# OperantFEDv5.net
KiCad netlist of a schematic drawn in EAGLE
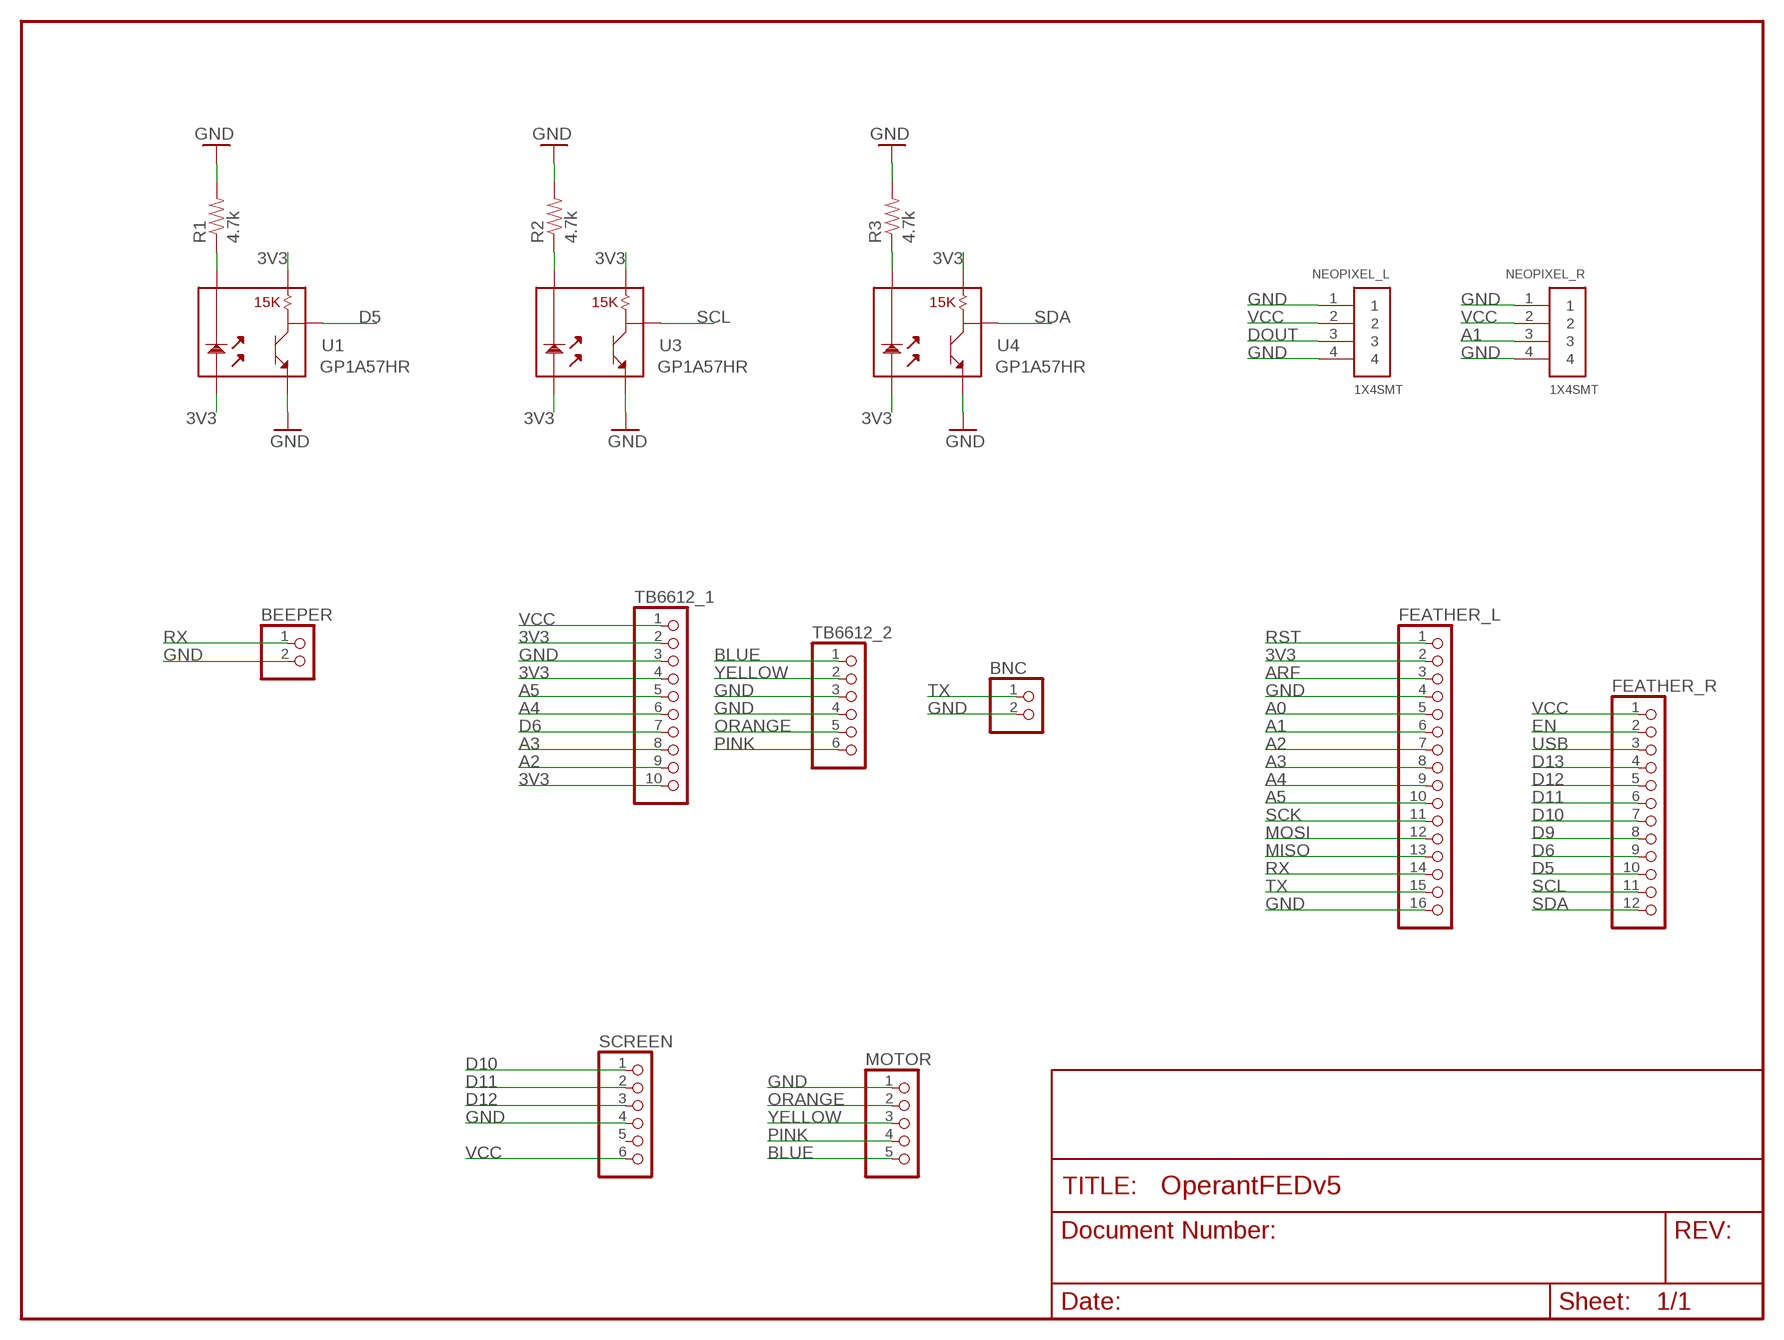
[diagram p0: schematic, sheet 1]

(export (version "E")
  (design (tool "Eeschema 10.0.6"))
  (components
    (comp (ref "BEEPER")
      (value "PINHD-1X2")
      (footprint "eagle-import:1X02")
      (libsource (lib "eagle-import") (part "PINHD-1X2"))
    )
    (comp (ref "BNC")
      (value "PINHD-1X2")
      (footprint "eagle-import:1X02")
      (libsource (lib "eagle-import") (part "PINHD-1X2"))
    )
    (comp (ref "FEATHER_L")
      (value "PINHD-1X16")
      (footprint "eagle-import:1X16")
      (libsource (lib "eagle-import") (part "PINHD-1X16"))
    )
    (comp (ref "FEATHER_R")
      (value "PINHD-1X12")
      (footprint "eagle-import:1X12")
      (libsource (lib "eagle-import") (part "PINHD-1X12"))
    )
    (comp (ref "MOTOR")
      (value "PINHD-1X5")
      (footprint "eagle-import:1X05")
      (libsource (lib "eagle-import") (part "PINHD-1X5"))
    )
    (comp (ref "NEOPIXEL_L")
      (value "1X4SMT")
      (footprint "eagle-import:1X4-SMT")
      (libsource (lib "eagle-import") (part "1X4SMT"))
    )
    (comp (ref "NEOPIXEL_R")
      (value "1X4SMT")
      (footprint "eagle-import:1X4-SMT")
      (libsource (lib "eagle-import") (part "1X4SMT"))
    )
    (comp (ref "R1")
      (value "4.7k")
      (footprint "eagle-import:AXIAL-0.3")
      (libsource (lib "eagle-import") (part "RESISTORPTH1"))
    )
    (comp (ref "R2")
      (value "4.7k")
      (footprint "eagle-import:AXIAL-0.3")
      (libsource (lib "eagle-import") (part "RESISTORPTH1"))
    )
    (comp (ref "R3")
      (value "4.7k")
      (footprint "eagle-import:AXIAL-0.3")
      (libsource (lib "eagle-import") (part "RESISTORPTH1"))
    )
    (comp (ref "SCREEN")
      (value "PINHD-1X6")
      (footprint "eagle-import:1X06")
      (libsource (lib "eagle-import") (part "PINHD-1X6"))
    )
    (comp (ref "TB6612_1")
      (value "PINHD-1X10")
      (footprint "eagle-import:1X10")
      (libsource (lib "eagle-import") (part "PINHD-1X10"))
    )
    (comp (ref "TB6612_2")
      (value "PINHD-1X6")
      (footprint "eagle-import:1X06")
      (libsource (lib "eagle-import") (part "PINHD-1X6"))
    )
    (comp (ref "U1")
      (value "GP1A57HR")
      (footprint "eagle-import:GP1A57HR")
      (libsource (lib "eagle-import") (part "GP1A57HR"))
    )
    (comp (ref "U3")
      (value "GP1A57HR")
      (footprint "eagle-import:GP1A57HR")
      (libsource (lib "eagle-import") (part "GP1A57HR"))
    )
    (comp (ref "U4")
      (value "GP1A57HR")
      (footprint "eagle-import:GP1A57HR")
      (libsource (lib "eagle-import") (part "GP1A57HR"))
    )
  )
  (nets
    (net (code "1") (name "/3V3") (class "Default")
      (node (ref "FEATHER_L") (pin "2") (pinfunction "2_2") (pintype "passive"))
      (node (ref "TB6612_1") (pin "10") (pinfunction "10_10") (pintype "passive"))
      (node (ref "TB6612_1") (pin "2") (pinfunction "2_2") (pintype "passive"))
      (node (ref "TB6612_1") (pin "4") (pinfunction "4_4") (pintype "passive"))
      (node (ref "U1") (pin "1") (pinfunction "1_1") (pintype "bidirectional"))
      (node (ref "U1") (pin "3") (pinfunction "3_3") (pintype "bidirectional"))
      (node (ref "U3") (pin "1") (pinfunction "1_1") (pintype "bidirectional"))
      (node (ref "U3") (pin "3") (pinfunction "3_3") (pintype "bidirectional"))
      (node (ref "U4") (pin "1") (pinfunction "1_1") (pintype "bidirectional"))
      (node (ref "U4") (pin "3") (pinfunction "3_3") (pintype "bidirectional"))
    )
    (net (code "2") (name "/A0") (class "Default")
      (node (ref "FEATHER_L") (pin "5") (pinfunction "5_5") (pintype "passive"))
    )
    (net (code "3") (name "/A1") (class "Default")
      (node (ref "FEATHER_L") (pin "6") (pinfunction "6_6") (pintype "passive"))
      (node (ref "NEOPIXEL_R") (pin "3") (pinfunction "3_3") (pintype "bidirectional"))
    )
    (net (code "4") (name "/A2") (class "Default")
      (node (ref "FEATHER_L") (pin "7") (pinfunction "7_7") (pintype "passive"))
      (node (ref "TB6612_1") (pin "9") (pinfunction "9_9") (pintype "passive"))
    )
    (net (code "5") (name "/A3") (class "Default")
      (node (ref "FEATHER_L") (pin "8") (pinfunction "8_8") (pintype "passive"))
      (node (ref "TB6612_1") (pin "8") (pinfunction "8_8") (pintype "passive"))
    )
    (net (code "6") (name "/A4") (class "Default")
      (node (ref "FEATHER_L") (pin "9") (pinfunction "9_9") (pintype "passive"))
      (node (ref "TB6612_1") (pin "6") (pinfunction "6_6") (pintype "passive"))
    )
    (net (code "7") (name "/A5") (class "Default")
      (node (ref "FEATHER_L") (pin "10") (pinfunction "10_10") (pintype "passive"))
      (node (ref "TB6612_1") (pin "5") (pinfunction "5_5") (pintype "passive"))
    )
    (net (code "8") (name "/ARF") (class "Default")
      (node (ref "FEATHER_L") (pin "3") (pinfunction "3_3") (pintype "passive"))
    )
    (net (code "9") (name "/BLUE") (class "Default")
      (node (ref "MOTOR") (pin "5") (pinfunction "5_5") (pintype "passive"))
      (node (ref "TB6612_2") (pin "1") (pinfunction "1_1") (pintype "passive"))
    )
    (net (code "10") (name "/D5") (class "Default")
      (node (ref "FEATHER_R") (pin "10") (pinfunction "10_10") (pintype "passive"))
      (node (ref "U1") (pin "4") (pinfunction "4_4") (pintype "bidirectional"))
    )
    (net (code "11") (name "/D6") (class "Default")
      (node (ref "FEATHER_R") (pin "9") (pinfunction "9_9") (pintype "passive"))
      (node (ref "TB6612_1") (pin "7") (pinfunction "7_7") (pintype "passive"))
    )
    (net (code "12") (name "/D9") (class "Default")
      (node (ref "FEATHER_R") (pin "8") (pinfunction "8_8") (pintype "passive"))
    )
    (net (code "13") (name "/D10") (class "Default")
      (node (ref "FEATHER_R") (pin "7") (pinfunction "7_7") (pintype "passive"))
      (node (ref "SCREEN") (pin "1") (pinfunction "1_1") (pintype "passive"))
    )
    (net (code "14") (name "/D11") (class "Default")
      (node (ref "FEATHER_R") (pin "6") (pinfunction "6_6") (pintype "passive"))
      (node (ref "SCREEN") (pin "2") (pinfunction "2_2") (pintype "passive"))
    )
    (net (code "15") (name "/D12") (class "Default")
      (node (ref "FEATHER_R") (pin "5") (pinfunction "5_5") (pintype "passive"))
      (node (ref "SCREEN") (pin "3") (pinfunction "3_3") (pintype "passive"))
    )
    (net (code "16") (name "/D13") (class "Default")
      (node (ref "FEATHER_R") (pin "4") (pinfunction "4_4") (pintype "passive"))
    )
    (net (code "17") (name "/DOUT") (class "Default")
      (node (ref "NEOPIXEL_L") (pin "3") (pinfunction "3_3") (pintype "bidirectional"))
    )
    (net (code "18") (name "/EN") (class "Default")
      (node (ref "FEATHER_R") (pin "2") (pinfunction "2_2") (pintype "passive"))
    )
    (net (code "19") (name "/MISO") (class "Default")
      (node (ref "FEATHER_L") (pin "13") (pinfunction "13_13") (pintype "passive"))
    )
    (net (code "20") (name "/MOSI") (class "Default")
      (node (ref "FEATHER_L") (pin "12") (pinfunction "12_12") (pintype "passive"))
    )
    (net (code "21") (name "/ORANGE") (class "Default")
      (node (ref "MOTOR") (pin "2") (pinfunction "2_2") (pintype "passive"))
      (node (ref "TB6612_2") (pin "5") (pinfunction "5_5") (pintype "passive"))
    )
    (net (code "22") (name "/PINK") (class "Default")
      (node (ref "MOTOR") (pin "4") (pinfunction "4_4") (pintype "passive"))
      (node (ref "TB6612_2") (pin "6") (pinfunction "6_6") (pintype "passive"))
    )
    (net (code "23") (name "/RST") (class "Default")
      (node (ref "FEATHER_L") (pin "1") (pinfunction "1_1") (pintype "passive"))
    )
    (net (code "24") (name "/RX") (class "Default")
      (node (ref "BEEPER") (pin "1") (pinfunction "1_1") (pintype "passive"))
      (node (ref "FEATHER_L") (pin "14") (pinfunction "14_14") (pintype "passive"))
    )
    (net (code "25") (name "/SCK") (class "Default")
      (node (ref "FEATHER_L") (pin "11") (pinfunction "11_11") (pintype "passive"))
    )
    (net (code "26") (name "/SCL") (class "Default")
      (node (ref "FEATHER_R") (pin "11") (pinfunction "11_11") (pintype "passive"))
      (node (ref "U3") (pin "4") (pinfunction "4_4") (pintype "bidirectional"))
    )
    (net (code "27") (name "/SDA") (class "Default")
      (node (ref "FEATHER_R") (pin "12") (pinfunction "12_12") (pintype "passive"))
      (node (ref "U4") (pin "4") (pinfunction "4_4") (pintype "bidirectional"))
    )
    (net (code "28") (name "/TX") (class "Default")
      (node (ref "BNC") (pin "1") (pinfunction "1_1") (pintype "passive"))
      (node (ref "FEATHER_L") (pin "15") (pinfunction "15_15") (pintype "passive"))
    )
    (net (code "29") (name "/USB") (class "Default")
      (node (ref "FEATHER_R") (pin "3") (pinfunction "3_3") (pintype "passive"))
    )
    (net (code "30") (name "/VCC") (class "Default")
      (node (ref "FEATHER_R") (pin "1") (pinfunction "1_1") (pintype "passive"))
      (node (ref "NEOPIXEL_L") (pin "2") (pinfunction "2_2") (pintype "bidirectional"))
      (node (ref "NEOPIXEL_R") (pin "2") (pinfunction "2_2") (pintype "bidirectional"))
      (node (ref "SCREEN") (pin "6") (pinfunction "6_6") (pintype "passive"))
      (node (ref "TB6612_1") (pin "1") (pinfunction "1_1") (pintype "passive"))
    )
    (net (code "31") (name "/YELLOW") (class "Default")
      (node (ref "MOTOR") (pin "3") (pinfunction "3_3") (pintype "passive"))
      (node (ref "TB6612_2") (pin "2") (pinfunction "2_2") (pintype "passive"))
    )
    (net (code "32") (name "GND") (class "Default")
      (node (ref "BEEPER") (pin "2") (pinfunction "2_2") (pintype "passive"))
      (node (ref "BNC") (pin "2") (pinfunction "2_2") (pintype "passive"))
      (node (ref "FEATHER_L") (pin "16") (pinfunction "16_16") (pintype "passive"))
      (node (ref "FEATHER_L") (pin "4") (pinfunction "4_4") (pintype "passive"))
      (node (ref "MOTOR") (pin "1") (pinfunction "1_1") (pintype "passive"))
      (node (ref "NEOPIXEL_L") (pin "1") (pinfunction "1_1") (pintype "bidirectional"))
      (node (ref "NEOPIXEL_L") (pin "4") (pinfunction "4_4") (pintype "bidirectional"))
      (node (ref "NEOPIXEL_R") (pin "1") (pinfunction "1_1") (pintype "bidirectional"))
      (node (ref "NEOPIXEL_R") (pin "4") (pinfunction "4_4") (pintype "bidirectional"))
      (node (ref "R1") (pin "P$2") (pinfunction "2_P$2") (pintype "passive"))
      (node (ref "R2") (pin "P$2") (pinfunction "2_P$2") (pintype "passive"))
      (node (ref "R3") (pin "P$2") (pinfunction "2_P$2") (pintype "passive"))
      (node (ref "SCREEN") (pin "4") (pinfunction "4_4") (pintype "passive"))
      (node (ref "TB6612_1") (pin "3") (pinfunction "3_3") (pintype "passive"))
      (node (ref "TB6612_2") (pin "3") (pinfunction "3_3") (pintype "passive"))
      (node (ref "TB6612_2") (pin "4") (pinfunction "4_4") (pintype "passive"))
      (node (ref "U1") (pin "5") (pinfunction "5_5") (pintype "bidirectional"))
      (node (ref "U3") (pin "5") (pinfunction "5_5") (pintype "bidirectional"))
      (node (ref "U4") (pin "5") (pinfunction "5_5") (pintype "bidirectional"))
    )
    (net (code "33") (name "Net-(R1-1)") (class "Default")
      (node (ref "R1") (pin "P$1") (pinfunction "1_P$1") (pintype "passive"))
      (node (ref "U1") (pin "2") (pinfunction "2_2") (pintype "bidirectional"))
    )
    (net (code "34") (name "Net-(R2-1)") (class "Default")
      (node (ref "R2") (pin "P$1") (pinfunction "1_P$1") (pintype "passive"))
      (node (ref "U3") (pin "2") (pinfunction "2_2") (pintype "bidirectional"))
    )
    (net (code "35") (name "Net-(R3-1)") (class "Default")
      (node (ref "R3") (pin "P$1") (pinfunction "1_P$1") (pintype "passive"))
      (node (ref "U4") (pin "2") (pinfunction "2_2") (pintype "bidirectional"))
    )
    (net (code "36") (name "unconnected-(SCREEN-Pad5)") (class "Default")
      (node (ref "SCREEN") (pin "5") (pinfunction "5_5") (pintype "passive"))
    )
  )
)
